# front.net
KiCad netlist of a schematic drawn in EAGLE
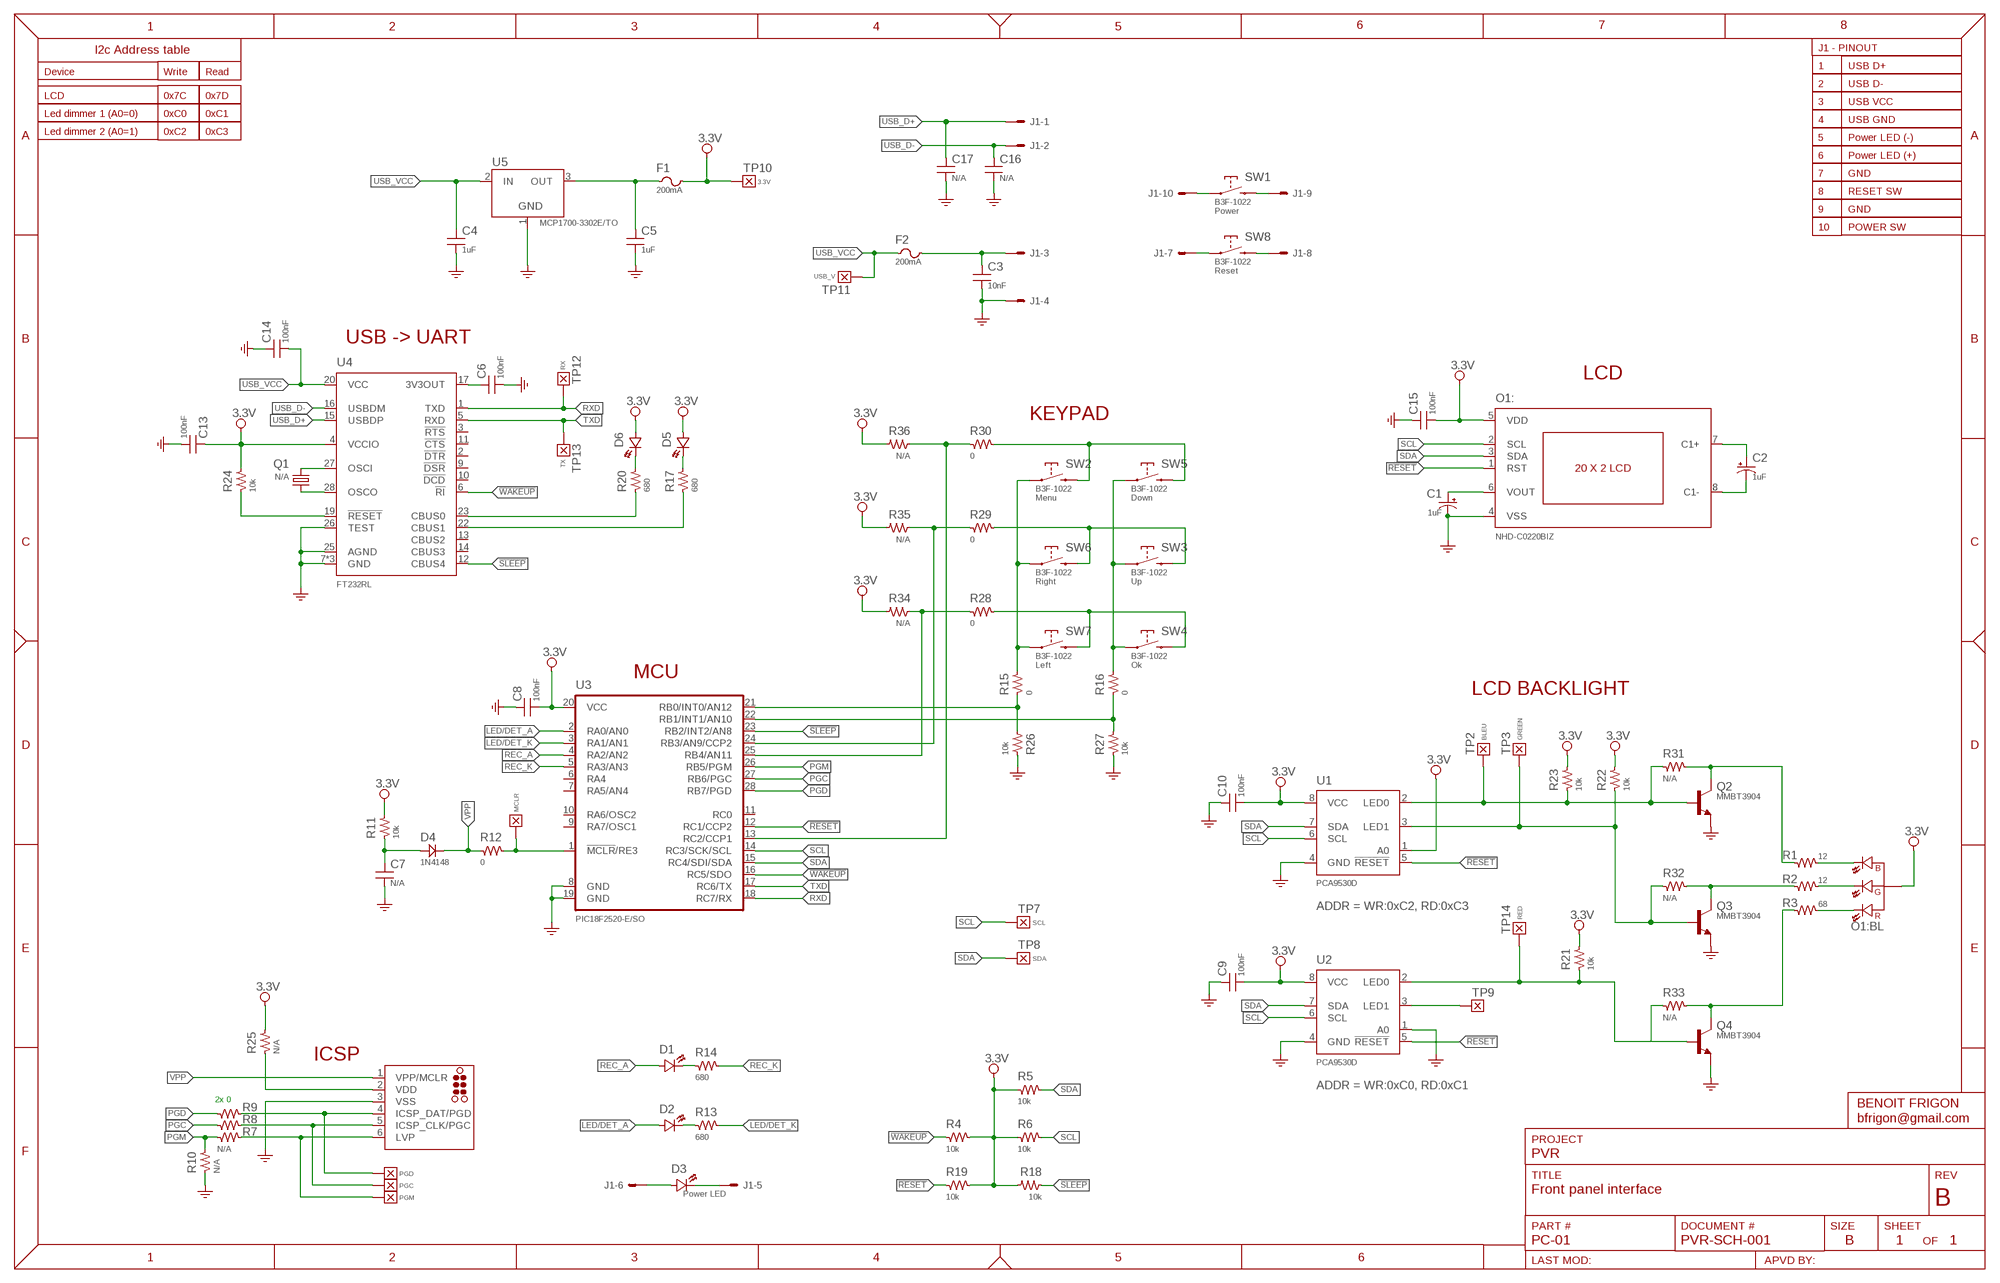
[diagram p0: schematic, sheet 1]

(export (version "E")
  (design (tool "Eeschema 10.0.6"))
  (components
    (comp (ref "C1")
      (value "1uF")
      (footprint "eagle-import:CAP_S0805")
      (libsource (lib "eagle-import") (part "CAP-E-S0805"))
    )
    (comp (ref "C2")
      (value "1uF")
      (footprint "eagle-import:CAP_S0805")
      (libsource (lib "eagle-import") (part "CAP-E-S0805"))
    )
    (comp (ref "C3")
      (value "10nF")
      (footprint "eagle-import:SMD_0805")
      (libsource (lib "eagle-import") (part "CAP-0805"))
    )
    (comp (ref "C4")
      (value "1uF")
      (footprint "eagle-import:SMD_0805")
      (libsource (lib "eagle-import") (part "CAP-0805"))
    )
    (comp (ref "C5")
      (value "1uF")
      (footprint "eagle-import:SMD_0805")
      (libsource (lib "eagle-import") (part "CAP-0805"))
    )
    (comp (ref "C6")
      (value "100nF")
      (footprint "eagle-import:SMD_0603")
      (libsource (lib "eagle-import") (part "CAP-0603"))
    )
    (comp (ref "C7")
      (value "N/A")
      (footprint "eagle-import:SMD_0603")
      (libsource (lib "eagle-import") (part "CAP-0603"))
    )
    (comp (ref "C8")
      (value "100nF")
      (footprint "eagle-import:SMD_0603")
      (libsource (lib "eagle-import") (part "CAP-0603"))
    )
    (comp (ref "C9")
      (value "100nF")
      (footprint "eagle-import:SMD_0603")
      (libsource (lib "eagle-import") (part "CAP-0603"))
    )
    (comp (ref "C10")
      (value "100nF")
      (footprint "eagle-import:SMD_0603")
      (libsource (lib "eagle-import") (part "CAP-0603"))
    )
    (comp (ref "C13")
      (value "100nF")
      (footprint "eagle-import:SMD_0603")
      (libsource (lib "eagle-import") (part "CAP-0603"))
    )
    (comp (ref "C14")
      (value "100nF")
      (footprint "eagle-import:SMD_0603")
      (description "{DESCRIPTION} - SMT 0603 - {value}")
      (fields (field (name "PACKAGE") "SMT 0603"))
      (libsource (lib "eagle-import") (part "CAP-0603"))
    )
    (comp (ref "C15")
      (value "100nF")
      (footprint "eagle-import:SMD_0603")
      (libsource (lib "eagle-import") (part "CAP-0603"))
    )
    (comp (ref "C16")
      (value "N/A")
      (footprint "eagle-import:SMD_0603")
      (libsource (lib "eagle-import") (part "CAP-0603"))
    )
    (comp (ref "C17")
      (value "N/A")
      (footprint "eagle-import:SMD_0603")
      (libsource (lib "eagle-import") (part "CAP-0603"))
    )
    (comp (ref "D1")
      (value "{ATTR:COLOR}")
      (footprint "eagle-import:LED_2X5")
      (fields (field (name "COLOR") "Red"))
      (libsource (lib "eagle-import") (part "LED-2X5"))
    )
    (comp (ref "D2")
      (value "{ATTR:COLOR}")
      (footprint "eagle-import:LED_2X5")
      (libsource (lib "eagle-import") (part "LED-2X5"))
    )
    (comp (ref "D3")
      (value "{ATTR:COLOR}")
      (footprint "eagle-import:LED_2X5")
      (fields (field (name "ID") "Power LED"))
      (libsource (lib "eagle-import") (part "LED-2X5"))
    )
    (comp (ref "D4")
      (value "1N4148")
      (footprint "eagle-import:DIODE_0603")
      (libsource (lib "eagle-import") (part "DIODE-0603"))
    )
    (comp (ref "D5")
      (value "LED-0805")
      (footprint "eagle-import:CHIPLED_0805")
      (description "{DESCRIPTION} Chip 0805 - {ATTR:COLOR}")
      (fields (field (name "COLOR") "Green") (field (name "PACKAGE") "SMT 0805") (field (name "SKU") "-"))
      (libsource (lib "eagle-import") (part "LED-0805"))
    )
    (comp (ref "D6")
      (value "LED-0805")
      (footprint "eagle-import:CHIPLED_0805")
      (libsource (lib "eagle-import") (part "LED-0805"))
    )
    (comp (ref "F1")
      (value "200mA")
      (footprint "eagle-import:SMD_1206")
      (libsource (lib "eagle-import") (part "FUSE1206"))
    )
    (comp (ref "F2")
      (value "200mA")
      (footprint "eagle-import:SMD_1206")
      (libsource (lib "eagle-import") (part "FUSE1206"))
    )
    (comp (ref "J1")
      (value "DL-100-HEADER-10-V")
      (footprint "eagle-import:534206-5")
      (fields
        (field (name "MFG") "Tyco Electronics")
        (field (name "MFG_1") "Sullins Connector Solutions")
        (field (name "SKU") "SIP110-PPPC-D05-ST-BK")
      )
      (libsource (lib "eagle-import") (part "DL-100-HEADER-10-V"))
    )
    (comp (ref "J10")
      (value "TC2030-MCP")
      (footprint "eagle-import:TC2030-MCP")
      (fields (field (name "MFG") "Tag-Connect"))
      (libsource (lib "eagle-import") (part "TC2030-MCP"))
    )
    (comp (ref "O1")
      (value "NHD-C0220BIZ")
      (footprint "eagle-import:NHD-CO220BIZ")
      (fields (field (name "MFG") "Newheaven Display"))
      (libsource (lib "eagle-import") (part "NHD-C0220BIZ"))
    )
    (comp (ref "Q1")
      (value "N/A")
      (footprint "eagle-import:MM20SS")
      (libsource (lib "eagle-import") (part "XTALMM20SS"))
    )
    (comp (ref "Q2")
      (value "MMBT3904")
      (footprint "eagle-import:SOT23")
      (libsource (lib "eagle-import") (part "MMBT3904"))
    )
    (comp (ref "Q3")
      (value "MMBT3904")
      (footprint "eagle-import:SOT23")
      (libsource (lib "eagle-import") (part "MMBT3904"))
    )
    (comp (ref "Q4")
      (value "MMBT3904")
      (footprint "eagle-import:SOT23")
      (libsource (lib "eagle-import") (part "MMBT3904"))
    )
    (comp (ref "R1")
      (value "12")
      (footprint "eagle-import:SMD_1206")
      (description "{DESCRIPTION} - SMT 1206 - {VALUE}")
      (fields (field (name "PACKAGE") "SMT 1206"))
      (libsource (lib "eagle-import") (part "RES-1206"))
    )
    (comp (ref "R2")
      (value "12")
      (footprint "eagle-import:SMD_1206")
      (description "{DESCRIPTION} - SMT 1206 - {VALUE}")
      (fields (field (name "PACKAGE") "SMT 1206"))
      (libsource (lib "eagle-import") (part "RES-1206"))
    )
    (comp (ref "R3")
      (value "68")
      (footprint "eagle-import:SMD_1206")
      (description "{DESCRIPTION} - SMT 1206 - {VALUE}")
      (fields (field (name "PACKAGE") "SMT 1206"))
      (libsource (lib "eagle-import") (part "RES-1206"))
    )
    (comp (ref "R4")
      (value "10k")
      (footprint "eagle-import:SMD_0805")
      (libsource (lib "eagle-import") (part "RES-0805"))
    )
    (comp (ref "R5")
      (value "10k")
      (footprint "eagle-import:SMD_0805")
      (libsource (lib "eagle-import") (part "RES-0805"))
    )
    (comp (ref "R6")
      (value "10k")
      (footprint "eagle-import:SMD_0805")
      (libsource (lib "eagle-import") (part "RES-0805"))
    )
    (comp (ref "R7")
      (value "N/A")
      (footprint "eagle-import:SMD_0603")
      (description "{DESCRIPTION} - SMT 0603 - {VALUE}")
      (fields (field (name "PACKAGE") "SMT 0603"))
      (libsource (lib "eagle-import") (part "RES-0603"))
    )
    (comp (ref "R8")
      (value "0")
      (footprint "eagle-import:SMD_0603")
      (description "{DESCRIPTION} - SMT 0603 - {VALUE}")
      (fields (field (name "PACKAGE") "SMT 0603"))
      (libsource (lib "eagle-import") (part "RES-0603"))
    )
    (comp (ref "R9")
      (value "0")
      (footprint "eagle-import:SMD_0603")
      (description "{DESCRIPTION} - SMT 0603 - {VALUE}")
      (fields (field (name "PACKAGE") "SMT 0603"))
      (libsource (lib "eagle-import") (part "RES-0603"))
    )
    (comp (ref "R10")
      (value "N/A")
      (footprint "eagle-import:SMD_0603")
      (description "{DESCRIPTION} - SMT 0603 - {VALUE}")
      (fields (field (name "PACKAGE") "SMT 0603"))
      (libsource (lib "eagle-import") (part "RES-0603"))
    )
    (comp (ref "R11")
      (value "10k")
      (footprint "eagle-import:SMD_0603")
      (libsource (lib "eagle-import") (part "RES-0603"))
    )
    (comp (ref "R12")
      (value "0")
      (footprint "eagle-import:SMD_0603")
      (libsource (lib "eagle-import") (part "RES-0603"))
    )
    (comp (ref "R13")
      (value "680")
      (footprint "eagle-import:SMD_0805")
      (libsource (lib "eagle-import") (part "RES-0805"))
    )
    (comp (ref "R14")
      (value "680")
      (footprint "eagle-import:SMD_0805")
      (description "{DESCRIPTION} - SMT 0805 - {VALUE}")
      (fields (field (name "PACKAGE") "SMT 0805"))
      (libsource (lib "eagle-import") (part "RES-0805"))
    )
    (comp (ref "R15")
      (value "0")
      (footprint "eagle-import:SMD_0805")
      (description "{DESCRIPTION} - SMT 0805 - {VALUE}")
      (fields (field (name "PACKAGE") "SMT 0805"))
      (libsource (lib "eagle-import") (part "RES-0805"))
    )
    (comp (ref "R16")
      (value "0")
      (footprint "eagle-import:SMD_0805")
      (libsource (lib "eagle-import") (part "RES-0805"))
    )
    (comp (ref "R17")
      (value "680")
      (footprint "eagle-import:SMD_0805")
      (description "{DESCRIPTION} - SMT 0805 - {VALUE}")
      (fields (field (name "PACKAGE") "SMT 0805"))
      (libsource (lib "eagle-import") (part "RES-0805"))
    )
    (comp (ref "R18")
      (value "10k")
      (footprint "eagle-import:SMD_0805")
      (description "{DESCRIPTION} - SMT 0805 - {VALUE}")
      (fields (field (name "PACKAGE") "SMT 0805"))
      (libsource (lib "eagle-import") (part "RES-0805"))
    )
    (comp (ref "R19")
      (value "10k")
      (footprint "eagle-import:SMD_0805")
      (description "{DESCRIPTION} - SMT 0805 - {VALUE}")
      (fields (field (name "PACKAGE") "SMT 0805"))
      (libsource (lib "eagle-import") (part "RES-0805"))
    )
    (comp (ref "R20")
      (value "680")
      (footprint "eagle-import:SMD_0805")
      (libsource (lib "eagle-import") (part "RES-0805"))
    )
    (comp (ref "R21")
      (value "10k")
      (footprint "eagle-import:SMD_0805")
      (libsource (lib "eagle-import") (part "RES-0805"))
    )
    (comp (ref "R22")
      (value "10k")
      (footprint "eagle-import:SMD_0805")
      (libsource (lib "eagle-import") (part "RES-0805"))
    )
    (comp (ref "R23")
      (value "10k")
      (footprint "eagle-import:SMD_0805")
      (libsource (lib "eagle-import") (part "RES-0805"))
    )
    (comp (ref "R24")
      (value "10k")
      (footprint "eagle-import:SMD_0603")
      (libsource (lib "eagle-import") (part "RES-0603"))
    )
    (comp (ref "R25")
      (value "N/A")
      (footprint "eagle-import:SMD_0603")
      (libsource (lib "eagle-import") (part "RES-0603"))
    )
    (comp (ref "R26")
      (value "10k")
      (footprint "eagle-import:SMD_0603")
      (libsource (lib "eagle-import") (part "RES-0603"))
    )
    (comp (ref "R27")
      (value "10k")
      (footprint "eagle-import:SMD_0603")
      (libsource (lib "eagle-import") (part "RES-0603"))
    )
    (comp (ref "R28")
      (value "0")
      (footprint "eagle-import:SMD_0603")
      (libsource (lib "eagle-import") (part "RES-0603"))
    )
    (comp (ref "R29")
      (value "0")
      (footprint "eagle-import:SMD_0805")
      (description "{DESCRIPTION} - SMT 0805 - {VALUE}")
      (fields (field (name "PACKAGE") "SMT 0805"))
      (libsource (lib "eagle-import") (part "RES-0805"))
    )
    (comp (ref "R30")
      (value "0")
      (footprint "eagle-import:SMD_0805")
      (description "{DESCRIPTION} - SMT 0805 - {VALUE}")
      (fields (field (name "PACKAGE") "SMT 0805"))
      (libsource (lib "eagle-import") (part "RES-0805"))
    )
    (comp (ref "R31")
      (value "N/A")
      (footprint "eagle-import:SMD_1206")
      (libsource (lib "eagle-import") (part "RES-1206"))
    )
    (comp (ref "R32")
      (value "N/A")
      (footprint "eagle-import:SMD_1206")
      (libsource (lib "eagle-import") (part "RES-1206"))
    )
    (comp (ref "R33")
      (value "N/A")
      (footprint "eagle-import:SMD_1206")
      (libsource (lib "eagle-import") (part "RES-1206"))
    )
    (comp (ref "R34")
      (value "N/A")
      (footprint "eagle-import:SMD_0603")
      (libsource (lib "eagle-import") (part "RES-0603"))
    )
    (comp (ref "R35")
      (value "N/A")
      (footprint "eagle-import:SMD_0603")
      (libsource (lib "eagle-import") (part "RES-0603"))
    )
    (comp (ref "R36")
      (value "N/A")
      (footprint "eagle-import:SMD_0603")
      (libsource (lib "eagle-import") (part "RES-0603"))
    )
    (comp (ref "SW1")
      (value "B3F-1022")
      (footprint "eagle-import:B3F-10XX")
      (fields (field (name "MFG") "Omron Electronics") (field (name "KEY") "Power"))
      (libsource (lib "eagle-import") (part "B3F-?1022"))
    )
    (comp (ref "SW2")
      (value "B3F-1022")
      (footprint "eagle-import:B3F-10XX")
      (fields (field (name "MFG") "Omron Electronics") (field (name "KEY") "Menu"))
      (libsource (lib "eagle-import") (part "B3F-?1022"))
    )
    (comp (ref "SW3")
      (value "B3F-1022")
      (footprint "eagle-import:B3F-10XX")
      (fields (field (name "MFG") "Omron Electronics") (field (name "KEY") "Up"))
      (libsource (lib "eagle-import") (part "B3F-?1022"))
    )
    (comp (ref "SW4")
      (value "B3F-1022")
      (footprint "eagle-import:B3F-10XX")
      (fields (field (name "MFG") "Omron Electronics") (field (name "KEY") "Ok"))
      (libsource (lib "eagle-import") (part "B3F-?1022"))
    )
    (comp (ref "SW5")
      (value "B3F-1022")
      (footprint "eagle-import:B3F-10XX")
      (fields (field (name "MFG") "Omron Electronics") (field (name "KEY") "Down"))
      (libsource (lib "eagle-import") (part "B3F-?1022"))
    )
    (comp (ref "SW6")
      (value "B3F-1022")
      (footprint "eagle-import:B3F-10XX")
      (fields (field (name "MFG") "Omron Electronics") (field (name "KEY") "Right"))
      (libsource (lib "eagle-import") (part "B3F-?1022"))
    )
    (comp (ref "SW7")
      (value "B3F-1022")
      (footprint "eagle-import:B3F-10XX")
      (fields (field (name "MFG") "Omron Electronics") (field (name "KEY") "Left"))
      (libsource (lib "eagle-import") (part "B3F-?1022"))
    )
    (comp (ref "SW8")
      (value "B3F-1022")
      (footprint "eagle-import:B3F-10XX")
      (fields (field (name "MFG") "Omron Electronics") (field (name "KEY") "Reset"))
      (libsource (lib "eagle-import") (part "B3F-?1022"))
    )
    (comp (ref "TP1")
      (value "MCLR")
      (footprint "eagle-import:TP_050")
      (libsource (lib "eagle-import") (part "TEST_POINT-050"))
    )
    (comp (ref "TP2")
      (value "BLEU")
      (footprint "eagle-import:TP_050")
      (fields (field (name "NO_BOM") "1"))
      (libsource (lib "eagle-import") (part "TEST_POINT-050"))
    )
    (comp (ref "TP3")
      (value "GREEN")
      (footprint "eagle-import:TP_050")
      (fields (field (name "NO_BOM") "1"))
      (libsource (lib "eagle-import") (part "TEST_POINT-050"))
    )
    (comp (ref "TP4")
      (value "PGD")
      (footprint "eagle-import:TP_050")
      (libsource (lib "eagle-import") (part "TEST_POINT-050"))
    )
    (comp (ref "TP5")
      (value "PGC")
      (footprint "eagle-import:TP_050")
      (libsource (lib "eagle-import") (part "TEST_POINT-050"))
    )
    (comp (ref "TP6")
      (value "PGM")
      (footprint "eagle-import:TP_050")
      (libsource (lib "eagle-import") (part "TEST_POINT-050"))
    )
    (comp (ref "TP7")
      (value "SCL")
      (footprint "eagle-import:TP_050")
      (libsource (lib "eagle-import") (part "TEST_POINT-050"))
    )
    (comp (ref "TP8")
      (value "SDA")
      (footprint "eagle-import:TP_050")
      (libsource (lib "eagle-import") (part "TEST_POINT-050"))
    )
    (comp (ref "TP9")
      (value "TEST_POINT-050")
      (footprint "eagle-import:TP_050")
      (libsource (lib "eagle-import") (part "TEST_POINT-050"))
    )
    (comp (ref "TP10")
      (value "3.3V")
      (footprint "eagle-import:TP_050")
      (libsource (lib "eagle-import") (part "TEST_POINT-050"))
    )
    (comp (ref "TP11")
      (value "USB_V")
      (footprint "eagle-import:TP_050")
      (libsource (lib "eagle-import") (part "TEST_POINT-050"))
    )
    (comp (ref "TP12")
      (value "RX")
      (footprint "eagle-import:TP_050")
      (fields (field (name "NO_BOM") "1"))
      (libsource (lib "eagle-import") (part "TEST_POINT-050"))
    )
    (comp (ref "TP13")
      (value "TX")
      (footprint "eagle-import:TP_050")
      (fields (field (name "NO_BOM") "1"))
      (libsource (lib "eagle-import") (part "TEST_POINT-050"))
    )
    (comp (ref "TP14")
      (value "RED")
      (footprint "eagle-import:TP_050")
      (fields (field (name "NO_BOM") "1"))
      (libsource (lib "eagle-import") (part "TEST_POINT-050"))
    )
    (comp (ref "U1")
      (value "PCA9530D")
      (footprint "eagle-import:SOIC8")
      (fields (field (name "MFG") "NXP Semiconductors") (field (name "ADDR") "WR:0xC2, RD:0xC3"))
      (libsource (lib "eagle-import") (part "PCA9530D"))
    )
    (comp (ref "U2")
      (value "PCA9530D")
      (footprint "eagle-import:SOIC8")
      (fields (field (name "MFG") "NXP Semiconductors") (field (name "ADDR") "WR:0xC0, RD:0xC1"))
      (libsource (lib "eagle-import") (part "PCA9530D"))
    )
    (comp (ref "U3")
      (value "PIC18F2520-E/SO")
      (footprint "eagle-import:SOIC28")
      (libsource (lib "eagle-import") (part "PIC18F520-?E/SO2"))
    )
    (comp (ref "U4")
      (value "FT232RL")
      (footprint "eagle-import:SSOP28")
      (libsource (lib "eagle-import") (part "FT232RL"))
    )
    (comp (ref "U5")
      (value "MCP1700-3302E/TO")
      (footprint "eagle-import:TO92")
      (fields (field (name "MFG") "Microchip"))
      (libsource (lib "eagle-import") (part "MCP1700-?TO3302E/"))
    )
  )
  (nets
    (net (code "1") (name "/~{RESET}") (class "Default")
      (node (ref "O1") (pin "1") (pinfunction "RST_1") (pintype "bidirectional"))
      (node (ref "R19") (pin "1") (pinfunction "1_1") (pintype "passive"))
      (node (ref "U1") (pin "5") (pinfunction "~{RESET}_5") (pintype "input"))
      (node (ref "U2") (pin "5") (pinfunction "~{RESET}_5") (pintype "input"))
      (node (ref "U3") (pin "12") (pinfunction "RC1/CCP2_12") (pintype "bidirectional"))
    )
    (net (code "2") (name "/~{SLEEP}") (class "Default")
      (node (ref "R18") (pin "1") (pinfunction "1_1") (pintype "passive"))
      (node (ref "U3") (pin "23") (pinfunction "RB2/INT2/AN8_23") (pintype "bidirectional"))
      (node (ref "U4") (pin "12") (pinfunction "CBUS4_12") (pintype "bidirectional"))
    )
    (net (code "3") (name "/~{WAKEUP}") (class "Default")
      (node (ref "R4") (pin "1") (pinfunction "1_1") (pintype "passive"))
      (node (ref "U3") (pin "16") (pinfunction "RC5/SDO_16") (pintype "bidirectional"))
      (node (ref "U4") (pin "6") (pinfunction "~{RI}_6") (pintype "bidirectional"))
    )
    (net (code "4") (name "3.3V") (class "Default")
      (node (ref "C10") (pin "2") (pinfunction "2_2") (pintype "passive"))
      (node (ref "C13") (pin "1") (pinfunction "1_1") (pintype "passive"))
      (node (ref "C15") (pin "2") (pinfunction "2_2") (pintype "passive"))
      (node (ref "C8") (pin "2") (pinfunction "2_2") (pintype "passive"))
      (node (ref "C9") (pin "2") (pinfunction "2_2") (pintype "passive"))
      (node (ref "D5") (pin "A") (pinfunction "A_A") (pintype "passive"))
      (node (ref "D6") (pin "A") (pinfunction "A_A") (pintype "passive"))
      (node (ref "F1") (pin "2") (pinfunction "2_2") (pintype "passive"))
      (node (ref "O1") (pin "5") (pinfunction "VDD_5") (pintype "bidirectional"))
      (node (ref "O1") (pin "A") (pinfunction "A_A") (pintype "passive"))
      (node (ref "R11") (pin "2") (pinfunction "2_2") (pintype "passive"))
      (node (ref "R18") (pin "2") (pinfunction "2_2") (pintype "passive"))
      (node (ref "R19") (pin "2") (pinfunction "2_2") (pintype "passive"))
      (node (ref "R21") (pin "2") (pinfunction "2_2") (pintype "passive"))
      (node (ref "R22") (pin "2") (pinfunction "2_2") (pintype "passive"))
      (node (ref "R23") (pin "2") (pinfunction "2_2") (pintype "passive"))
      (node (ref "R24") (pin "2") (pinfunction "2_2") (pintype "passive"))
      (node (ref "R25") (pin "2") (pinfunction "2_2") (pintype "passive"))
      (node (ref "R34") (pin "2") (pinfunction "2_2") (pintype "passive"))
      (node (ref "R35") (pin "2") (pinfunction "2_2") (pintype "passive"))
      (node (ref "R36") (pin "2") (pinfunction "2_2") (pintype "passive"))
      (node (ref "R4") (pin "2") (pinfunction "2_2") (pintype "passive"))
      (node (ref "R5") (pin "1") (pinfunction "1_1") (pintype "passive"))
      (node (ref "R6") (pin "1") (pinfunction "1_1") (pintype "passive"))
      (node (ref "TP10") (pin "1") (pinfunction "P$1_1") (pintype "bidirectional"))
      (node (ref "U1") (pin "1") (pinfunction "A0_1") (pintype "bidirectional"))
      (node (ref "U1") (pin "8") (pinfunction "VCC_8") (pintype "power_in"))
      (node (ref "U2") (pin "8") (pinfunction "VCC_8") (pintype "power_in"))
      (node (ref "U3") (pin "20") (pinfunction "VCC_20") (pintype "power_in"))
      (node (ref "U4") (pin "4") (pinfunction "VCCIO_4") (pintype "bidirectional"))
    )
    (net (code "5") (name "GND") (class "Default")
      (node (ref "C1") (pin "-") (pinfunction "-_-") (pintype "passive"))
      (node (ref "C10") (pin "1") (pinfunction "1_1") (pintype "passive"))
      (node (ref "C13") (pin "2") (pinfunction "2_2") (pintype "passive"))
      (node (ref "C14") (pin "1") (pinfunction "1_1") (pintype "passive"))
      (node (ref "C15") (pin "1") (pinfunction "1_1") (pintype "passive"))
      (node (ref "C16") (pin "2") (pinfunction "2_2") (pintype "passive"))
      (node (ref "C17") (pin "2") (pinfunction "2_2") (pintype "passive"))
      (node (ref "C3") (pin "2") (pinfunction "2_2") (pintype "passive"))
      (node (ref "C4") (pin "2") (pinfunction "2_2") (pintype "passive"))
      (node (ref "C5") (pin "2") (pinfunction "2_2") (pintype "passive"))
      (node (ref "C6") (pin "2") (pinfunction "2_2") (pintype "passive"))
      (node (ref "C7") (pin "2") (pinfunction "2_2") (pintype "passive"))
      (node (ref "C8") (pin "1") (pinfunction "1_1") (pintype "passive"))
      (node (ref "C9") (pin "1") (pinfunction "1_1") (pintype "passive"))
      (node (ref "J1") (pin "4") (pinfunction "S_4") (pintype "bidirectional"))
      (node (ref "J10") (pin "3") (pinfunction "VSS_3") (pintype "power_in"))
      (node (ref "O1") (pin "4") (pinfunction "VSS_4") (pintype "bidirectional"))
      (node (ref "Q2") (pin "2") (pinfunction "E_2") (pintype "passive"))
      (node (ref "Q3") (pin "2") (pinfunction "E_2") (pintype "passive"))
      (node (ref "Q4") (pin "2") (pinfunction "E_2") (pintype "passive"))
      (node (ref "R10") (pin "1") (pinfunction "1_1") (pintype "passive"))
      (node (ref "R26") (pin "1") (pinfunction "1_1") (pintype "passive"))
      (node (ref "R27") (pin "1") (pinfunction "1_1") (pintype "passive"))
      (node (ref "U1") (pin "4") (pinfunction "GND_4") (pintype "power_in"))
      (node (ref "U2") (pin "1") (pinfunction "A0_1") (pintype "bidirectional"))
      (node (ref "U2") (pin "4") (pinfunction "GND_4") (pintype "power_in"))
      (node (ref "U3") (pin "19") (pinfunction "GND_19") (pintype "power_in"))
      (node (ref "U3") (pin "8") (pinfunction "GND_8") (pintype "power_in"))
      (node (ref "U4") (pin "18") (pinfunction "GND_18") (pintype "bidirectional"))
      (node (ref "U4") (pin "21") (pinfunction "GND_21") (pintype "bidirectional"))
      (node (ref "U4") (pin "25") (pinfunction "AGND_25") (pintype "bidirectional"))
      (node (ref "U4") (pin "26") (pinfunction "TEST_26") (pintype "bidirectional"))
      (node (ref "U4") (pin "7") (pinfunction "GND_7") (pintype "bidirectional"))
      (node (ref "U5") (pin "1") (pinfunction "GND_1") (pintype "power_in"))
    )
    (net (code "6") (name "LED{slash}DET_A") (class "Default")
      (node (ref "D2") (pin "A") (pinfunction "A_A") (pintype "passive"))
      (node (ref "U3") (pin "2") (pinfunction "RA0/AN0_2") (pintype "bidirectional"))
    )
    (net (code "7") (name "LED{slash}DET_K") (class "Default")
      (node (ref "R13") (pin "2") (pinfunction "2_2") (pintype "passive"))
      (node (ref "U3") (pin "3") (pinfunction "RA1/AN1_3") (pintype "bidirectional"))
    )
    (net (code "8") (name "Net-(C7-Pad1)") (class "Default")
      (node (ref "C7") (pin "1") (pinfunction "1_1") (pintype "passive"))
      (node (ref "D4") (pin "A") (pinfunction "A_A") (pintype "passive"))
      (node (ref "R11") (pin "1") (pinfunction "1_1") (pintype "passive"))
    )
    (net (code "9") (name "Net-(D1-PadK)") (class "Default")
      (node (ref "D1") (pin "K") (pinfunction "K_K") (pintype "passive"))
      (node (ref "R14") (pin "1") (pinfunction "1_1") (pintype "passive"))
    )
    (net (code "10") (name "Net-(D2-PadK)") (class "Default")
      (node (ref "D2") (pin "K") (pinfunction "K_K") (pintype "passive"))
      (node (ref "R13") (pin "1") (pinfunction "1_1") (pintype "passive"))
    )
    (net (code "11") (name "Net-(D5-PadK)") (class "Default")
      (node (ref "D5") (pin "K") (pinfunction "K_K") (pintype "passive"))
      (node (ref "R17") (pin "2") (pinfunction "2_2") (pintype "passive"))
    )
    (net (code "12") (name "Net-(D6-PadK)") (class "Default")
      (node (ref "D6") (pin "K") (pinfunction "K_K") (pintype "passive"))
      (node (ref "R20") (pin "2") (pinfunction "2_2") (pintype "passive"))
    )
    (net (code "13") (name "Net-(J1B-S)") (class "Default")
      (node (ref "J1") (pin "10") (pinfunction "S_10") (pintype "bidirectional"))
      (node (ref "SW1") (pin "3") (pinfunction "1_3") (pintype "passive"))
      (node (ref "SW1") (pin "4") (pinfunction "1_4") (pintype "passive"))
    )
    (net (code "14") (name "Net-(J1D-S)") (class "Default")
      (node (ref "C3") (pin "1") (pinfunction "1_1") (pintype "passive"))
      (node (ref "F2") (pin "2") (pinfunction "2_2") (pintype "passive"))
      (node (ref "J1") (pin "3") (pinfunction "S_3") (pintype "bidirectional"))
    )
    (net (code "15") (name "Net-(J1F-S)") (class "Default")
      (node (ref "D3") (pin "K") (pinfunction "K_K") (pintype "passive"))
      (node (ref "J1") (pin "5") (pinfunction "S_5") (pintype "bidirectional"))
    )
    (net (code "16") (name "Net-(J1G-S)") (class "Default")
      (node (ref "D3") (pin "A") (pinfunction "A_A") (pintype "passive"))
      (node (ref "J1") (pin "6") (pinfunction "S_6") (pintype "bidirectional"))
    )
    (net (code "17") (name "Net-(J1H-S)") (class "Default")
      (node (ref "J1") (pin "7") (pinfunction "S_7") (pintype "bidirectional"))
      (node (ref "SW8") (pin "3") (pinfunction "1_3") (pintype "passive"))
      (node (ref "SW8") (pin "4") (pinfunction "1_4") (pintype "passive"))
    )
    (net (code "18") (name "Net-(J1I-S)") (class "Default")
      (node (ref "J1") (pin "8") (pinfunction "S_8") (pintype "bidirectional"))
      (node (ref "SW8") (pin "1") (pinfunction "2_1") (pintype "passive"))
      (node (ref "SW8") (pin "2") (pinfunction "2_2") (pintype "passive"))
    )
    (net (code "19") (name "Net-(J1J-S)") (class "Default")
      (node (ref "J1") (pin "9") (pinfunction "S_9") (pintype "bidirectional"))
      (node (ref "SW1") (pin "1") (pinfunction "2_1") (pintype "passive"))
      (node (ref "SW1") (pin "2") (pinfunction "2_2") (pintype "passive"))
    )
    (net (code "20") (name "Net-(J10-ICSP_CLK{slash}PGC)") (class "Default")
      (node (ref "J10") (pin "5") (pinfunction "ICSP_CLK/PGC_5") (pintype "output"))
      (node (ref "R8") (pin "2") (pinfunction "2_2") (pintype "passive"))
      (node (ref "TP5") (pin "1") (pinfunction "P$1_1") (pintype "bidirectional"))
    )
    (net (code "21") (name "Net-(J10-ICSP_DAT{slash}PGD)") (class "Default")
      (node (ref "J10") (pin "4") (pinfunction "ICSP_DAT/PGD_4") (pintype "bidirectional"))
      (node (ref "R9") (pin "2") (pinfunction "2_2") (pintype "passive"))
      (node (ref "TP4") (pin "1") (pinfunction "P$1_1") (pintype "bidirectional"))
    )
    (net (code "22") (name "Net-(J10-LVP)") (class "Default")
      (node (ref "J10") (pin "6") (pinfunction "LVP_6") (pintype "bidirectional"))
      (node (ref "R7") (pin "2") (pinfunction "2_2") (pintype "passive"))
      (node (ref "TP6") (pin "1") (pinfunction "P$1_1") (pintype "bidirectional"))
    )
    (net (code "23") (name "Net-(J10-VDD)") (class "Default")
      (node (ref "J10") (pin "2") (pinfunction "VDD_2") (pintype "power_in"))
      (node (ref "R25") (pin "1") (pinfunction "1_1") (pintype "passive"))
    )
    (net (code "24") (name "Net-(O1-PadBK)") (class "Default")
      (node (ref "O1") (pin "BK") (pinfunction "BK_BK") (pintype "passive"))
      (node (ref "R1") (pin "2") (pinfunction "2_2") (pintype "passive"))
    )
    (net (code "25") (name "Net-(O1-PadGK)") (class "Default")
      (node (ref "O1") (pin "GK") (pinfunction "GK_GK") (pintype "passive"))
      (node (ref "R2") (pin "2") (pinfunction "2_2") (pintype "passive"))
    )
    (net (code "26") (name "Net-(O1-PadRK)") (class "Default")
      (node (ref "O1") (pin "RK") (pinfunction "RK_RK") (pintype "passive"))
      (node (ref "R3") (pin "2") (pinfunction "2_2") (pintype "passive"))
    )
    (net (code "27") (name "Net-(O1A-C1+)") (class "Default")
      (node (ref "C2") (pin "+") (pinfunction "+_+") (pintype "passive"))
      (node (ref "O1") (pin "7") (pinfunction "C1+_7") (pintype "bidirectional"))
    )
    (net (code "28") (name "Net-(O1A-C1-)") (class "Default")
      (node (ref "C2") (pin "-") (pinfunction "-_-") (pintype "passive"))
      (node (ref "O1") (pin "8") (pinfunction "C1-_8") (pintype "bidirectional"))
    )
    (net (code "29") (name "Net-(O1A-VOUT)") (class "Default")
      (node (ref "C1") (pin "+") (pinfunction "+_+") (pintype "passive"))
      (node (ref "O1") (pin "6") (pinfunction "VOUT_6") (pintype "bidirectional"))
    )
    (net (code "30") (name "Net-(Q1-2)") (class "Default")
      (node (ref "Q1") (pin "4") (pinfunction "2_4") (pintype "passive"))
      (node (ref "U4") (pin "28") (pinfunction "OSCO_28") (pintype "bidirectional"))
    )
    (net (code "31") (name "Net-(Q2-B)") (class "Default")
      (node (ref "Q2") (pin "1") (pinfunction "B_1") (pintype "passive"))
      (node (ref "R23") (pin "1") (pinfunction "1_1") (pintype "passive"))
      (node (ref "R31") (pin "1") (pinfunction "1_1") (pintype "passive"))
      (node (ref "TP2") (pin "1") (pinfunction "P$1_1") (pintype "bidirectional"))
      (node (ref "U1") (pin "2") (pinfunction "LED0_2") (pintype "output"))
    )
    (net (code "32") (name "Net-(Q2-C)") (class "Default")
      (node (ref "Q2") (pin "3") (pinfunction "C_3") (pintype "passive"))
      (node (ref "R1") (pin "1") (pinfunction "1_1") (pintype "passive"))
      (node (ref "R31") (pin "2") (pinfunction "2_2") (pintype "passive"))
    )
    (net (code "33") (name "Net-(Q3-B)") (class "Default")
      (node (ref "Q3") (pin "1") (pinfunction "B_1") (pintype "passive"))
      (node (ref "R22") (pin "1") (pinfunction "1_1") (pintype "passive"))
      (node (ref "R32") (pin "1") (pinfunction "1_1") (pintype "passive"))
      (node (ref "TP3") (pin "1") (pinfunction "P$1_1") (pintype "bidirectional"))
      (node (ref "U1") (pin "3") (pinfunction "LED1_3") (pintype "output"))
    )
    (net (code "34") (name "Net-(Q3-C)") (class "Default")
      (node (ref "Q3") (pin "3") (pinfunction "C_3") (pintype "passive"))
      (node (ref "R2") (pin "1") (pinfunction "1_1") (pintype "passive"))
      (node (ref "R32") (pin "2") (pinfunction "2_2") (pintype "passive"))
    )
    (net (code "35") (name "Net-(Q4-B)") (class "Default")
      (node (ref "Q4") (pin "1") (pinfunction "B_1") (pintype "passive"))
      (node (ref "R21") (pin "1") (pinfunction "1_1") (pintype "passive"))
      (node (ref "R33") (pin "1") (pinfunction "1_1") (pintype "passive"))
      (node (ref "TP14") (pin "1") (pinfunction "P$1_1") (pintype "bidirectional"))
      (node (ref "U2") (pin "2") (pinfunction "LED0_2") (pintype "output"))
    )
    (net (code "36") (name "Net-(Q4-C)") (class "Default")
      (node (ref "Q4") (pin "3") (pinfunction "C_3") (pintype "passive"))
      (node (ref "R3") (pin "1") (pinfunction "1_1") (pintype "passive"))
      (node (ref "R33") (pin "2") (pinfunction "2_2") (pintype "passive"))
    )
    (net (code "37") (name "Net-(R15-Pad2)") (class "Default")
      (node (ref "R15") (pin "2") (pinfunction "2_2") (pintype "passive"))
      (node (ref "SW2") (pin "3") (pinfunction "1_3") (pintype "passive"))
      (node (ref "SW2") (pin "4") (pinfunction "1_4") (pintype "passive"))
      (node (ref "SW6") (pin "3") (pinfunction "1_3") (pintype "passive"))
      (node (ref "SW6") (pin "4") (pinfunction "1_4") (pintype "passive"))
      (node (ref "SW7") (pin "3") (pinfunction "1_3") (pintype "passive"))
      (node (ref "SW7") (pin "4") (pinfunction "1_4") (pintype "passive"))
    )
    (net (code "38") (name "Net-(R16-Pad2)") (class "Default")
      (node (ref "R16") (pin "2") (pinfunction "2_2") (pintype "passive"))
      (node (ref "SW3") (pin "3") (pinfunction "1_3") (pintype "passive"))
      (node (ref "SW3") (pin "4") (pinfunction "1_4") (pintype "passive"))
      (node (ref "SW4") (pin "3") (pinfunction "1_3") (pintype "passive"))
      (node (ref "SW4") (pin "4") (pinfunction "1_4") (pintype "passive"))
      (node (ref "SW5") (pin "3") (pinfunction "1_3") (pintype "passive"))
      (node (ref "SW5") (pin "4") (pinfunction "1_4") (pintype "passive"))
    )
    (net (code "39") (name "Net-(R28-Pad2)") (class "Default")
      (node (ref "R28") (pin "2") (pinfunction "2_2") (pintype "passive"))
      (node (ref "SW4") (pin "1") (pinfunction "2_1") (pintype "passive"))
      (node (ref "SW4") (pin "2") (pinfunction "2_2") (pintype "passive"))
      (node (ref "SW7") (pin "1") (pinfunction "2_1") (pintype "passive"))
      (node (ref "SW7") (pin "2") (pinfunction "2_2") (pintype "passive"))
    )
    (net (code "40") (name "Net-(R29-Pad2)") (class "Default")
      (node (ref "R29") (pin "2") (pinfunction "2_2") (pintype "passive"))
      (node (ref "SW3") (pin "1") (pinfunction "2_1") (pintype "passive"))
      (node (ref "SW3") (pin "2") (pinfunction "2_2") (pintype "passive"))
      (node (ref "SW6") (pin "1") (pinfunction "2_1") (pintype "passive"))
      (node (ref "SW6") (pin "2") (pinfunction "2_2") (pintype "passive"))
    )
    (net (code "41") (name "Net-(R30-Pad2)") (class "Default")
      (node (ref "R30") (pin "2") (pinfunction "2_2") (pintype "passive"))
      (node (ref "SW2") (pin "1") (pinfunction "2_1") (pintype "passive"))
      (node (ref "SW2") (pin "2") (pinfunction "2_2") (pintype "passive"))
      (node (ref "SW5") (pin "1") (pinfunction "2_1") (pintype "passive"))
      (node (ref "SW5") (pin "2") (pinfunction "2_2") (pintype "passive"))
    )
    (net (code "42") (name "Net-(TP1-P$1)") (class "Default")
      (node (ref "R12") (pin "2") (pinfunction "2_2") (pintype "passive"))
      (node (ref "TP1") (pin "1") (pinfunction "P$1_1") (pintype "bidirectional"))
      (node (ref "U3") (pin "1") (pinfunction "~{MCLR}/RE3_1") (pintype "bidirectional"))
    )
    (net (code "43") (name "Net-(TP9-P$1)") (class "Default")
      (node (ref "TP9") (pin "1") (pinfunction "P$1_1") (pintype "bidirectional"))
      (node (ref "U2") (pin "3") (pinfunction "LED1_3") (pintype "output"))
    )
    (net (code "44") (name "Net-(U3-RB0{slash}INT0{slash}AN12)") (class "Default")
      (node (ref "R15") (pin "1") (pinfunction "1_1") (pintype "passive"))
      (node (ref "R26") (pin "2") (pinfunction "2_2") (pintype "passive"))
      (node (ref "U3") (pin "21") (pinfunction "RB0/INT0/AN12_21") (pintype "bidirectional"))
    )
    (net (code "45") (name "Net-(U3-RB1{slash}INT1{slash}AN10)") (class "Default")
      (node (ref "R16") (pin "1") (pinfunction "1_1") (pintype "passive"))
      (node (ref "R27") (pin "2") (pinfunction "2_2") (pintype "passive"))
      (node (ref "U3") (pin "22") (pinfunction "RB1/INT1/AN10_22") (pintype "bidirectional"))
    )
    (net (code "46") (name "Net-(U3-RB3{slash}AN9{slash}CCP2)") (class "Default")
      (node (ref "R29") (pin "1") (pinfunction "1_1") (pintype "passive"))
      (node (ref "R35") (pin "1") (pinfunction "1_1") (pintype "passive"))
      (node (ref "U3") (pin "24") (pinfunction "RB3/AN9/CCP2_24") (pintype "bidirectional"))
    )
    (net (code "47") (name "Net-(U3-RB4{slash}AN11)") (class "Default")
      (node (ref "R28") (pin "1") (pinfunction "1_1") (pintype "passive"))
      (node (ref "R34") (pin "1") (pinfunction "1_1") (pintype "passive"))
      (node (ref "U3") (pin "25") (pinfunction "RB4/AN11_25") (pintype "bidirectional"))
    )
    (net (code "48") (name "Net-(U3-RC2{slash}CCP1)") (class "Default")
      (node (ref "R30") (pin "1") (pinfunction "1_1") (pintype "passive"))
      (node (ref "R36") (pin "1") (pinfunction "1_1") (pintype "passive"))
      (node (ref "U3") (pin "13") (pinfunction "RC2/CCP1_13") (pintype "bidirectional"))
    )
    (net (code "49") (name "Net-(U4-3V3OUT)") (class "Default")
      (node (ref "C6") (pin "1") (pinfunction "1_1") (pintype "passive"))
      (node (ref "U4") (pin "17") (pinfunction "3V3OUT_17") (pintype "bidirectional"))
    )
    (net (code "50") (name "Net-(U4-CBUS0)") (class "Default")
      (node (ref "R20") (pin "1") (pinfunction "1_1") (pintype "passive"))
      (node (ref "U4") (pin "23") (pinfunction "CBUS0_23") (pintype "bidirectional"))
    )
    (net (code "51") (name "Net-(U4-CBUS1)") (class "Default")
      (node (ref "R17") (pin "1") (pinfunction "1_1") (pintype "passive"))
      (node (ref "U4") (pin "22") (pinfunction "CBUS1_22") (pintype "bidirectional"))
    )
    (net (code "52") (name "Net-(U4-OSCI)") (class "Default")
      (node (ref "Q1") (pin "1") (pinfunction "1_1") (pintype "passive"))
      (node (ref "U4") (pin "27") (pinfunction "OSCI_27") (pintype "bidirectional"))
    )
    (net (code "53") (name "Net-(U4-~{RESET})") (class "Default")
      (node (ref "R24") (pin "1") (pinfunction "1_1") (pintype "passive"))
      (node (ref "U4") (pin "19") (pinfunction "~{RESET}_19") (pintype "bidirectional"))
    )
    (net (code "54") (name "Net-(U5-OUT)") (class "Default")
      (node (ref "C5") (pin "1") (pinfunction "1_1") (pintype "passive"))
      (node (ref "F1") (pin "1") (pinfunction "1_1") (pintype "passive"))
      (node (ref "U5") (pin "3") (pinfunction "OUT_3") (pintype "power_in"))
    )
    (net (code "55") (name "PGC") (class "Default")
      (node (ref "R8") (pin "1") (pinfunction "1_1") (pintype "passive"))
      (node (ref "U3") (pin "27") (pinfunction "RB6/PGC_27") (pintype "bidirectional"))
    )
    (net (code "56") (name "PGD") (class "Default")
      (node (ref "R9") (pin "1") (pinfunction "1_1") (pintype "passive"))
      (node (ref "U3") (pin "28") (pinfunction "RB7/PGD_28") (pintype "bidirectional"))
    )
    (net (code "57") (name "PGM") (class "Default")
      (node (ref "R10") (pin "2") (pinfunction "2_2") (pintype "passive"))
      (node (ref "R7") (pin "1") (pinfunction "1_1") (pintype "passive"))
      (node (ref "U3") (pin "26") (pinfunction "RB5/PGM_26") (pintype "bidirectional"))
    )
    (net (code "58") (name "REC_A") (class "Default")
      (node (ref "D1") (pin "A") (pinfunction "A_A") (pintype "passive"))
      (node (ref "U3") (pin "4") (pinfunction "RA2/AN2_4") (pintype "bidirectional"))
    )
    (net (code "59") (name "REC_K") (class "Default")
      (node (ref "R14") (pin "2") (pinfunction "2_2") (pintype "passive"))
      (node (ref "U3") (pin "5") (pinfunction "RA3/AN3_5") (pintype "bidirectional"))
    )
    (net (code "60") (name "RXD") (class "Default")
      (node (ref "TP12") (pin "1") (pinfunction "P$1_1") (pintype "bidirectional"))
      (node (ref "U3") (pin "18") (pinfunction "RC7/RX_18") (pintype "bidirectional"))
      (node (ref "U4") (pin "1") (pinfunction "TXD_1") (pintype "bidirectional"))
    )
    (net (code "61") (name "SCL") (class "Default")
      (node (ref "O1") (pin "2") (pinfunction "SCL_2") (pintype "bidirectional"))
      (node (ref "R6") (pin "2") (pinfunction "2_2") (pintype "passive"))
      (node (ref "TP7") (pin "1") (pinfunction "P$1_1") (pintype "bidirectional"))
      (node (ref "U1") (pin "6") (pinfunction "SCL_6") (pintype "input"))
      (node (ref "U2") (pin "6") (pinfunction "SCL_6") (pintype "input"))
      (node (ref "U3") (pin "14") (pinfunction "RC3/SCK/SCL_14") (pintype "bidirectional"))
    )
    (net (code "62") (name "SDA") (class "Default")
      (node (ref "O1") (pin "3") (pinfunction "SDA_3") (pintype "bidirectional"))
      (node (ref "R5") (pin "2") (pinfunction "2_2") (pintype "passive"))
      (node (ref "TP8") (pin "1") (pinfunction "P$1_1") (pintype "bidirectional"))
      (node (ref "U1") (pin "7") (pinfunction "SDA_7") (pintype "bidirectional"))
      (node (ref "U2") (pin "7") (pinfunction "SDA_7") (pintype "bidirectional"))
      (node (ref "U3") (pin "15") (pinfunction "RC4/SDI/SDA_15") (pintype "bidirectional"))
    )
    (net (code "63") (name "TXD") (class "Default")
      (node (ref "TP13") (pin "1") (pinfunction "P$1_1") (pintype "bidirectional"))
      (node (ref "U3") (pin "17") (pinfunction "RC6/TX_17") (pintype "bidirectional"))
      (node (ref "U4") (pin "5") (pinfunction "RXD_5") (pintype "bidirectional"))
    )
    (net (code "64") (name "USB_D+") (class "Default")
      (node (ref "C17") (pin "1") (pinfunction "1_1") (pintype "passive"))
      (node (ref "J1") (pin "1") (pinfunction "S_1") (pintype "bidirectional"))
      (node (ref "U4") (pin "15") (pinfunction "USBDP_15") (pintype "bidirectional"))
    )
    (net (code "65") (name "USB_D-") (class "Default")
      (node (ref "C16") (pin "1") (pinfunction "1_1") (pintype "passive"))
      (node (ref "J1") (pin "2") (pinfunction "S_2") (pintype "bidirectional"))
      (node (ref "U4") (pin "16") (pinfunction "USBDM_16") (pintype "bidirectional"))
    )
    (net (code "66") (name "USB_VCC") (class "Default")
      (node (ref "C14") (pin "2") (pinfunction "2_2") (pintype "passive"))
      (node (ref "C4") (pin "1") (pinfunction "1_1") (pintype "passive"))
      (node (ref "F2") (pin "1") (pinfunction "1_1") (pintype "passive"))
      (node (ref "TP11") (pin "1") (pinfunction "P$1_1") (pintype "bidirectional"))
      (node (ref "U4") (pin "20") (pinfunction "VCC_20") (pintype "bidirectional"))
      (node (ref "U5") (pin "2") (pinfunction "IN_2") (pintype "power_in"))
    )
    (net (code "67") (name "VPP") (class "Default")
      (node (ref "D4") (pin "K") (pinfunction "K_K") (pintype "passive"))
      (node (ref "J10") (pin "1") (pinfunction "VPP/MCLR_1") (pintype "passive"))
      (node (ref "R12") (pin "1") (pinfunction "1_1") (pintype "passive"))
    )
    (net (code "68") (name "unconnected-(U3-RA4-Pad6)") (class "Default")
      (node (ref "U3") (pin "6") (pinfunction "RA4_6") (pintype "bidirectional"))
    )
    (net (code "69") (name "unconnected-(U3-RA5{slash}AN4-Pad7)") (class "Default")
      (node (ref "U3") (pin "7") (pinfunction "RA5/AN4_7") (pintype "bidirectional"))
    )
    (net (code "70") (name "unconnected-(U3-RA6{slash}OSC2-Pad10)") (class "Default")
      (node (ref "U3") (pin "10") (pinfunction "RA6/OSC2_10") (pintype "bidirectional"))
    )
    (net (code "71") (name "unconnected-(U3-RA7{slash}OSC1-Pad9)") (class "Default")
      (node (ref "U3") (pin "9") (pinfunction "RA7/OSC1_9") (pintype "bidirectional"))
    )
    (net (code "72") (name "unconnected-(U3-RC0-Pad11)") (class "Default")
      (node (ref "U3") (pin "11") (pinfunction "RC0_11") (pintype "bidirectional"))
    )
    (net (code "73") (name "unconnected-(U4-CBUS2-Pad13)") (class "Default")
      (node (ref "U4") (pin "13") (pinfunction "CBUS2_13") (pintype "bidirectional"))
    )
    (net (code "74") (name "unconnected-(U4-CBUS3-Pad14)") (class "Default")
      (node (ref "U4") (pin "14") (pinfunction "CBUS3_14") (pintype "bidirectional"))
    )
    (net (code "75") (name "unconnected-(U4-~{CTS}-Pad11)") (class "Default")
      (node (ref "U4") (pin "11") (pinfunction "~{CTS}_11") (pintype "bidirectional"))
    )
    (net (code "76") (name "unconnected-(U4-~{DCD}-Pad10)") (class "Default")
      (node (ref "U4") (pin "10") (pinfunction "~{DCD}_10") (pintype "bidirectional"))
    )
    (net (code "77") (name "unconnected-(U4-~{DSR}-Pad9)") (class "Default")
      (node (ref "U4") (pin "9") (pinfunction "~{DSR}_9") (pintype "bidirectional"))
    )
    (net (code "78") (name "unconnected-(U4-~{DTR}-Pad2)") (class "Default")
      (node (ref "U4") (pin "2") (pinfunction "~{DTR}_2") (pintype "bidirectional"))
    )
    (net (code "79") (name "unconnected-(U4-~{RTS}-Pad3)") (class "Default")
      (node (ref "U4") (pin "3") (pinfunction "~{RTS}_3") (pintype "bidirectional"))
    )
  )
)
